# EPass_2026-04-09_20-28-50.net
KiCad netlist of a schematic drawn in EasyEDA Pro
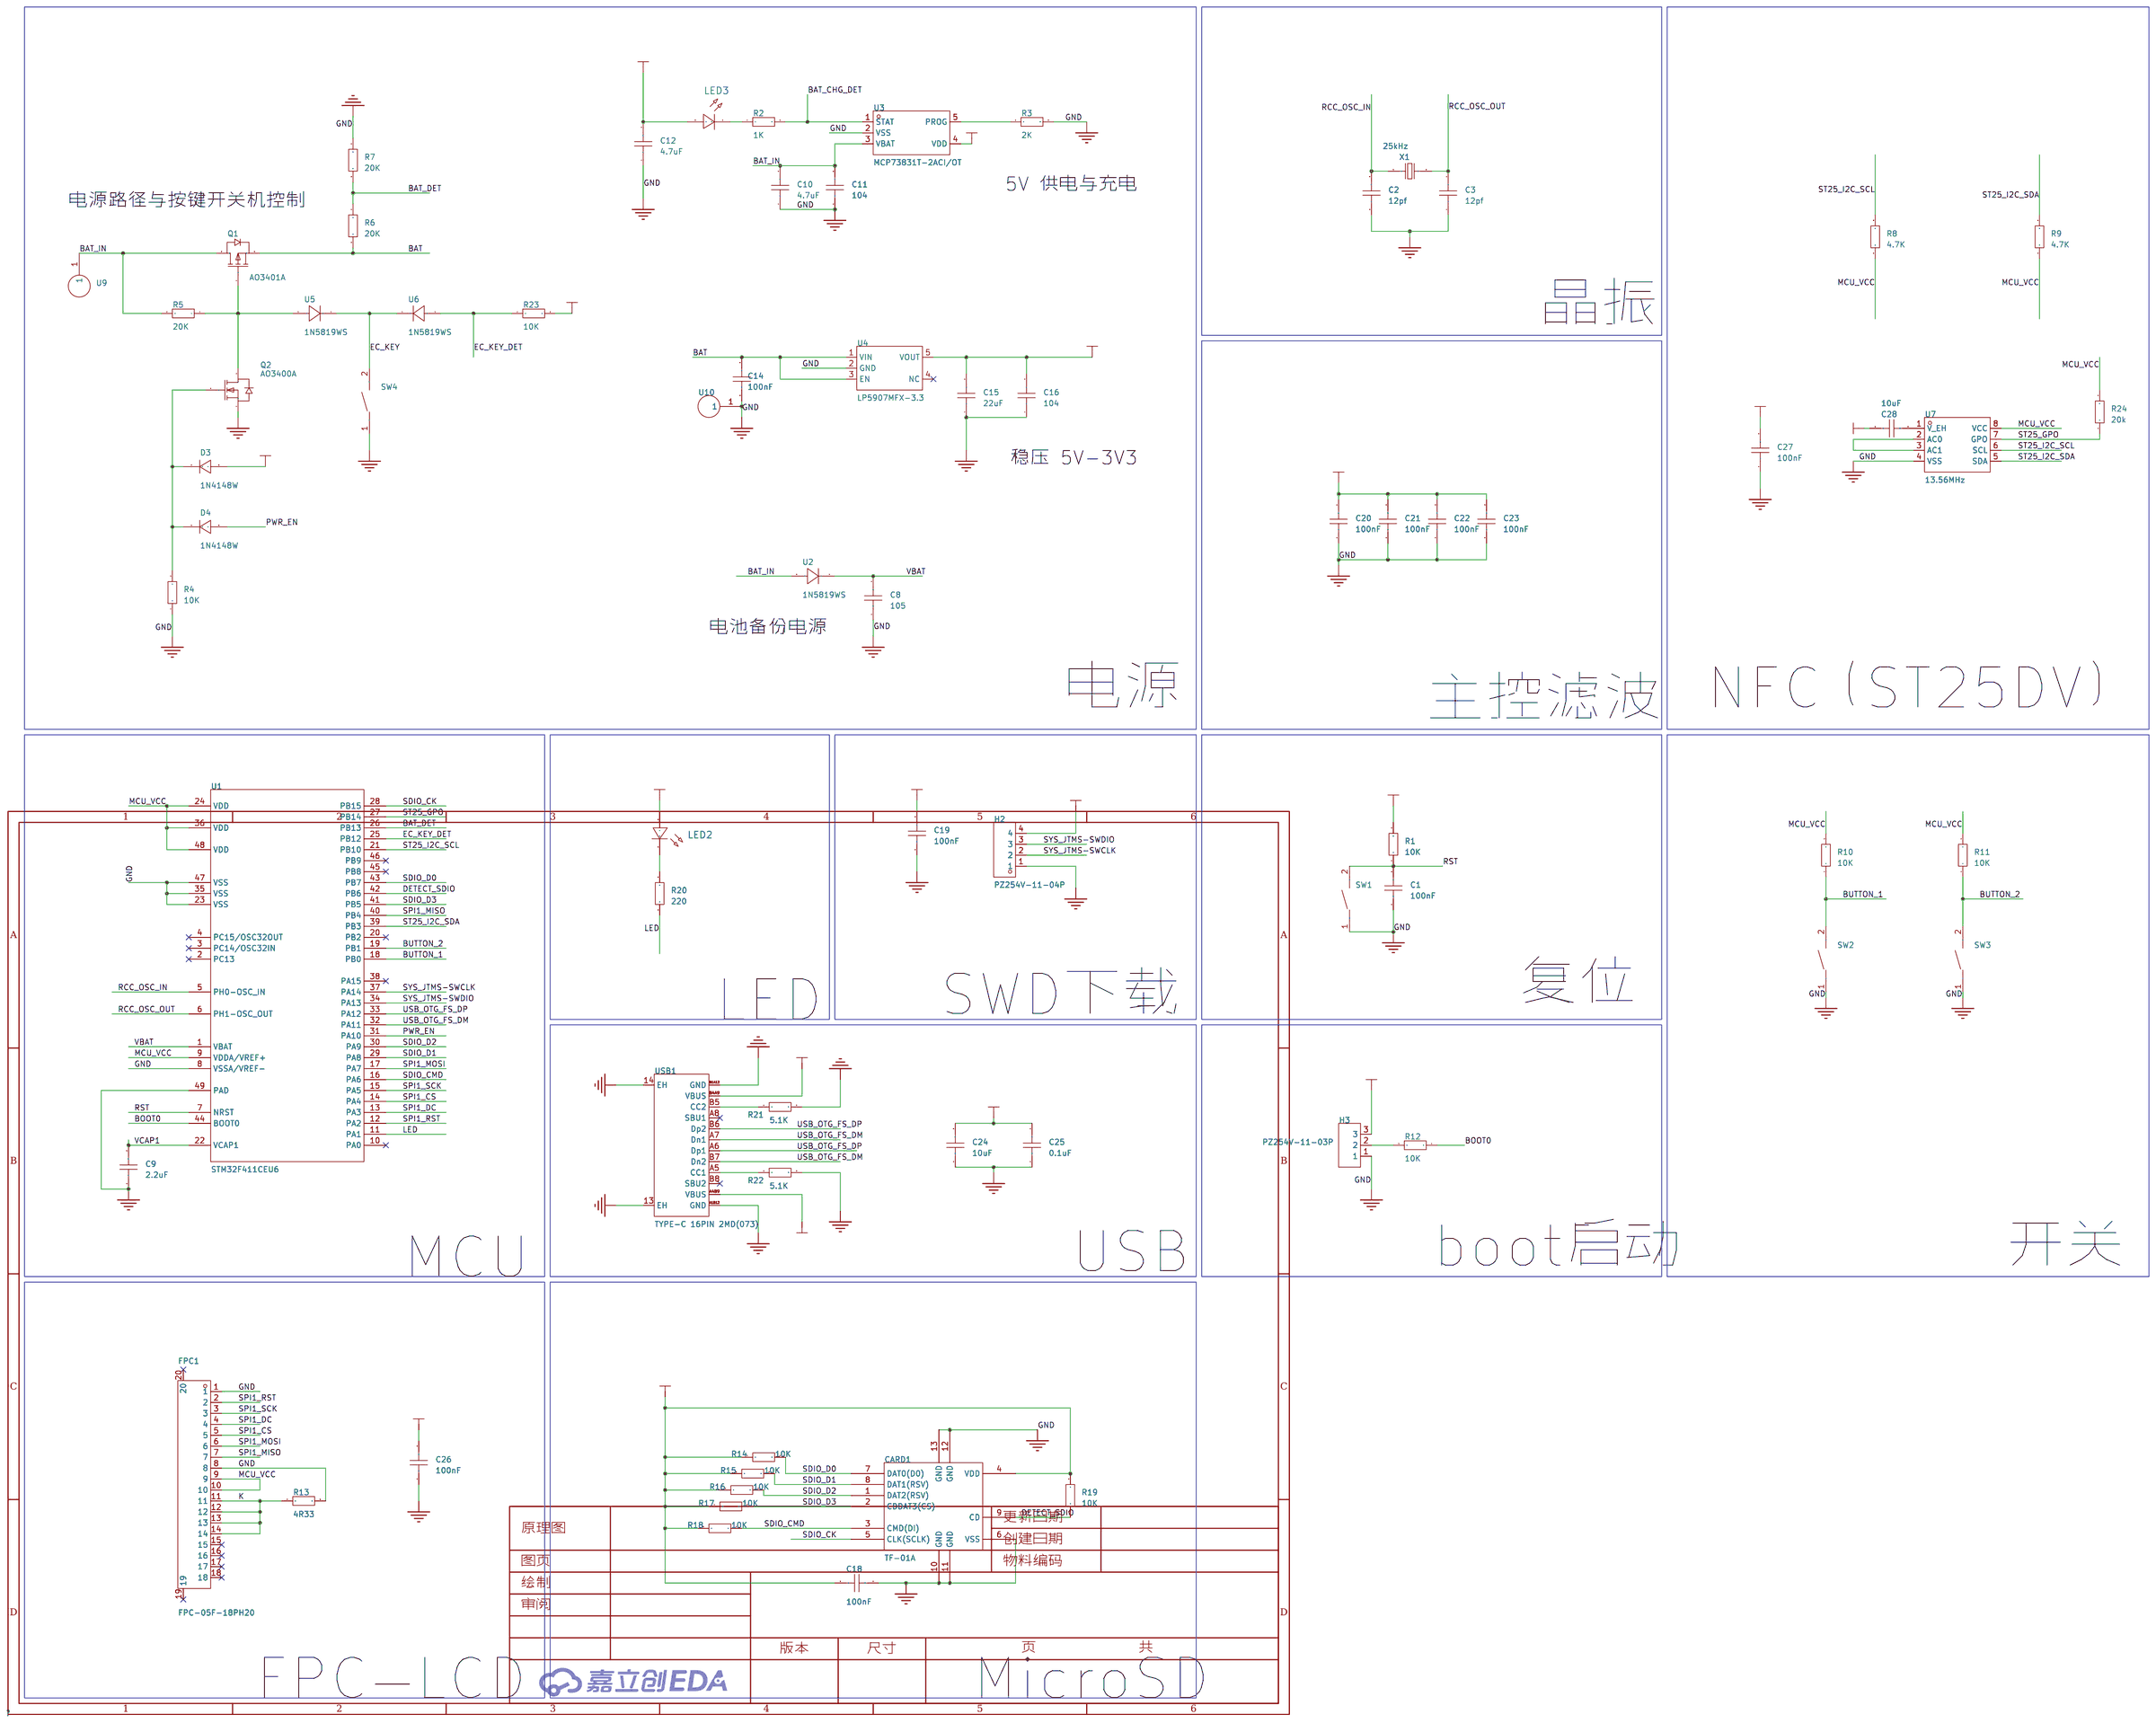
[diagram p0: schematic sheet]

(export (version "E")
  (design (tool "Eeschema 10.0.6"))
  (components
    (comp (ref "C1")
      (value "100nF")
      (footprint "easyedapro:C0603")
      (libsource (lib "easyedapro") (part "Capacitance"))
    )
    (comp (ref "C2")
      (value "12pf")
      (footprint "easyedapro:C0603")
      (libsource (lib "easyedapro") (part "Capacitance"))
    )
    (comp (ref "C3")
      (value "12pf")
      (footprint "easyedapro:C0603")
      (libsource (lib "easyedapro") (part "Capacitance"))
    )
    (comp (ref "C8")
      (value "105")
      (footprint "easyedapro:C0603")
      (libsource (lib "easyedapro") (part "Capacitance"))
    )
    (comp (ref "C9")
      (value "2.2uF")
      (footprint "easyedapro:C0603")
      (libsource (lib "easyedapro") (part "Capacitance"))
    )
    (comp (ref "C10")
      (value "4.7uF")
      (footprint "easyedapro:C0603")
      (libsource (lib "easyedapro") (part "Capacitance"))
    )
    (comp (ref "C11")
      (value "104")
      (footprint "easyedapro:C0603")
      (libsource (lib "easyedapro") (part "Capacitance"))
    )
    (comp (ref "C12")
      (value "4.7uF")
      (footprint "easyedapro:C0603")
      (libsource (lib "easyedapro") (part "Capacitance"))
    )
    (comp (ref "C14")
      (value "100nF")
      (footprint "easyedapro:C0603")
      (libsource (lib "easyedapro") (part "Capacitance"))
    )
    (comp (ref "C15")
      (value "22uF")
      (footprint "easyedapro:C0603")
      (libsource (lib "easyedapro") (part "Capacitance"))
    )
    (comp (ref "C16")
      (value "104")
      (footprint "easyedapro:C0603")
      (libsource (lib "easyedapro") (part "Capacitance"))
    )
    (comp (ref "C18")
      (value "100nF")
      (footprint "easyedapro:C0603")
      (libsource (lib "easyedapro") (part "Capacitance"))
    )
    (comp (ref "C19")
      (value "100nF")
      (footprint "easyedapro:C0603")
      (libsource (lib "easyedapro") (part "Capacitance"))
    )
    (comp (ref "C20")
      (value "100nF")
      (footprint "easyedapro:C0603")
      (libsource (lib "easyedapro") (part "Capacitance"))
    )
    (comp (ref "C21")
      (value "100nF")
      (footprint "easyedapro:C0603")
      (libsource (lib "easyedapro") (part "Capacitance"))
    )
    (comp (ref "C22")
      (value "100nF")
      (footprint "easyedapro:C0603")
      (libsource (lib "easyedapro") (part "Capacitance"))
    )
    (comp (ref "C23")
      (value "100nF")
      (footprint "easyedapro:C0603")
      (libsource (lib "easyedapro") (part "Capacitance"))
    )
    (comp (ref "C24")
      (value "10uF")
      (footprint "easyedapro:C0603")
      (libsource (lib "easyedapro") (part "Capacitance"))
    )
    (comp (ref "C25")
      (value "0.1uF")
      (footprint "easyedapro:C0603")
      (libsource (lib "easyedapro") (part "Capacitance"))
    )
    (comp (ref "C26")
      (value "100nF")
      (footprint "easyedapro:C0603")
      (libsource (lib "easyedapro") (part "Capacitance"))
    )
    (comp (ref "C27")
      (value "100nF")
      (footprint "easyedapro:C0603")
      (libsource (lib "easyedapro") (part "Capacitance"))
    )
    (comp (ref "C28")
      (value "10uF")
      (footprint "easyedapro:C0603")
      (libsource (lib "easyedapro") (part "Capacitance"))
    )
    (comp (ref "CARD1")
      (value "TF-01A")
      (footprint "easyedapro:TF-SMD_TF-01A")
      (description "卡连接方式:自弹式;卡类型:MicroSD卡(TF卡);连接器类型:卡座;本体最大高度:1.85mm;工作温度:-;")
      (fields (field (name "Manufacturer") "韩国韩荣"))
      (libsource (lib "easyedapro") (part "TF-01A"))
    )
    (comp (ref "D3")
      (value "1N4148W")
      (footprint "easyedapro:DO-35_BD2.0-L4.2-P8.20-D0.5-RD")
      (description "二极管配置:1个独立式;整流电流:200mA;直流反向耐压(Vr):100V;正向压降(Vf):1V@10mA;反向恢复时间(Trr):4ns;")
      (fields (field (name "Manufacturer") "R+O(宏嘉诚)"))
      (libsource (lib "easyedapro") (part "1N4148TR"))
    )
    (comp (ref "D4")
      (value "1N4148W")
      (footprint "easyedapro:DO-35_BD2.0-L4.2-P8.20-D0.5-RD")
      (description "二极管配置:1个独立式;整流电流:200mA;直流反向耐压(Vr):100V;正向压降(Vf):1V@10mA;反向恢复时间(Trr):4ns;")
      (fields (field (name "Manufacturer") "R+O(宏嘉诚)"))
      (libsource (lib "easyedapro") (part "1N4148TR"))
    )
    (comp (ref "FPC1")
      (value "FPC-05F-18PH20")
      (footprint "easyedapro:FPC-SMD_18P-P0.50_FPC-05F-18PH20")
      (description "锁定特性:翻盖式;触点类型:卧贴;触点数量:18P;间距:0.5mm;安装方式:下接;工作温度:-25°C~+85°C;")
      (fields (field (name "Manufacturer") "XUNPU(讯普)"))
      (libsource (lib "easyedapro") (part "FPC-05F-18PH20"))
    )
    (comp (ref "H2")
      (value "PZ254V-11-04P")
      (footprint "easyedapro:HDR-TH_4P-P2.54-V-M")
      (fields (field (name "Manufacturer") "XFCN(兴飞)"))
      (libsource (lib "easyedapro") (part "PZ254V-11-04P_C2691448"))
    )
    (comp (ref "H3")
      (value "PZ254V-11-03P")
      (footprint "easyedapro:HDR-TH_3P-P2.54-V-M_PZ254V-11-03P")
      (fields (field (name "Manufacturer") "XFCN(兴飞)"))
      (libsource (lib "easyedapro") (part "PZ254V-11-03P_C2937625"))
    )
    (comp (ref "LED2")
      (value "~")
      (footprint "easyedapro:LED_0603")
      (libsource (lib "easyedapro") (part "LED_R"))
    )
    (comp (ref "LED3")
      (value "~")
      (footprint "easyedapro:LED_0603")
      (libsource (lib "easyedapro") (part "LED_R"))
    )
    (comp (ref "Q1")
      (value "AO3401A")
      (footprint "easyedapro:SOT-23_L2.9-W1.3-P1.90-LS2.4-BR")
      (fields (field (name "Manufacturer") "AOS"))
      (libsource (lib "easyedapro") (part "AO3401A"))
    )
    (comp (ref "Q2")
      (value "AO3400A")
      (footprint "easyedapro:SOT-23-3_L2.9-W1.3-P1.90-LS2.4-BR")
      (description "数量:-;漏源电压(Vdss):30V;连续漏极电流(Id):-;导通电阻(RDS(on)):48mΩ@2.5V;耗散功率(Pd):-;阈值电压(Vgs(th)):1.45V@250uA;")
      (fields (field (name "Manufacturer") "AOS"))
      (libsource (lib "easyedapro") (part "AO3400A"))
    )
    (comp (ref "R1") (value "10K") (footprint "easyedapro:R0603") (libsource (lib "easyedapro") (part "电阻")))
    (comp (ref "R2") (value "1K") (footprint "easyedapro:R0603") (libsource (lib "easyedapro") (part "电阻")))
    (comp (ref "R3") (value "2K") (footprint "easyedapro:R0603") (libsource (lib "easyedapro") (part "电阻")))
    (comp (ref "R4") (value "10K") (footprint "easyedapro:R0603") (libsource (lib "easyedapro") (part "电阻")))
    (comp (ref "R5") (value "20K") (footprint "easyedapro:R0603") (libsource (lib "easyedapro") (part "电阻")))
    (comp (ref "R6") (value "20K") (footprint "easyedapro:R0603") (libsource (lib "easyedapro") (part "电阻")))
    (comp (ref "R7") (value "20K") (footprint "easyedapro:R0603") (libsource (lib "easyedapro") (part "电阻")))
    (comp (ref "R8") (value "4.7K") (footprint "easyedapro:R0603") (libsource (lib "easyedapro") (part "电阻")))
    (comp (ref "R9") (value "4.7K") (footprint "easyedapro:R0603") (libsource (lib "easyedapro") (part "电阻")))
    (comp (ref "R10") (value "10K") (footprint "easyedapro:R0603") (libsource (lib "easyedapro") (part "电阻")))
    (comp (ref "R11") (value "10K") (footprint "easyedapro:R0603") (libsource (lib "easyedapro") (part "电阻")))
    (comp (ref "R12") (value "10K") (footprint "easyedapro:R0603") (libsource (lib "easyedapro") (part "电阻")))
    (comp (ref "R13")
      (value "4R33")
      (footprint "easyedapro:R0603")
      (libsource (lib "easyedapro") (part "电阻"))
    )
    (comp (ref "R14") (value "10K") (footprint "easyedapro:R0603") (libsource (lib "easyedapro") (part "电阻")))
    (comp (ref "R15") (value "10K") (footprint "easyedapro:R0603") (libsource (lib "easyedapro") (part "电阻")))
    (comp (ref "R16") (value "10K") (footprint "easyedapro:R0603") (libsource (lib "easyedapro") (part "电阻")))
    (comp (ref "R17") (value "10K") (footprint "easyedapro:R0603") (libsource (lib "easyedapro") (part "电阻")))
    (comp (ref "R18") (value "10K") (footprint "easyedapro:R0603") (libsource (lib "easyedapro") (part "电阻")))
    (comp (ref "R19") (value "10K") (footprint "easyedapro:R0603") (libsource (lib "easyedapro") (part "电阻")))
    (comp (ref "R20") (value "220") (footprint "easyedapro:R0603") (libsource (lib "easyedapro") (part "电阻")))
    (comp (ref "R21")
      (value "5.1K")
      (footprint "easyedapro:R0603")
      (libsource (lib "easyedapro") (part "电阻"))
    )
    (comp (ref "R22")
      (value "5.1K")
      (footprint "easyedapro:R0603")
      (libsource (lib "easyedapro") (part "电阻"))
    )
    (comp (ref "R23") (value "10K") (footprint "easyedapro:R0603") (libsource (lib "easyedapro") (part "电阻")))
    (comp (ref "R24") (value "20k") (footprint "easyedapro:R0603") (libsource (lib "easyedapro") (part "电阻")))
    (comp (ref "SW1")
      (value "TS-1088-AR02016")
      (footprint "easyedapro:SW-SMD_L3.9-W3.0-P4.45")
      (fields (field (name "Manufacturer") "XUNPU(讯普)"))
      (libsource (lib "easyedapro") (part "TS-1088-AR02016"))
    )
    (comp (ref "SW2")
      (value "TS-1088-AR02016")
      (footprint "easyedapro:SW-SMD_L3.9-W3.0-P4.45")
      (fields (field (name "Manufacturer") "XUNPU(讯普)"))
      (libsource (lib "easyedapro") (part "TS-1088-AR02016"))
    )
    (comp (ref "SW3")
      (value "TS-1088-AR02016")
      (footprint "easyedapro:SW-SMD_L3.9-W3.0-P4.45")
      (fields (field (name "Manufacturer") "XUNPU(讯普)"))
      (libsource (lib "easyedapro") (part "TS-1088-AR02016"))
    )
    (comp (ref "SW4")
      (value "TS-1088-AR02016")
      (footprint "easyedapro:SW-SMD_L3.9-W3.0-P4.45")
      (fields (field (name "Manufacturer") "XUNPU(讯普)"))
      (libsource (lib "easyedapro") (part "TS-1088-AR02016"))
    )
    (comp (ref "U1")
      (value "STM32F411CEU6")
      (footprint "easyedapro:UFQFPN-48_L7.0-W7.0-P0.50-BL-EP")
      (description "CPU内核:ARM-M4;CPU最大主频:100MHz;应用领域:-;")
      (fields (field (name "Manufacturer") "ST(意法半导体)"))
      (libsource (lib "easyedapro") (part "STM32F411CEU6"))
    )
    (comp (ref "U2")
      (value "1N5819WS")
      (footprint "easyedapro:SMA_L4.3-W2.6-LS5.1-RD")
      (fields (field (name "Manufacturer") "Hottech(合科泰)"))
      (libsource (lib "easyedapro") (part "1N4007_C9900004759"))
    )
    (comp (ref "U3")
      (value "MCP73831T-2ACI/OT")
      (footprint "easyedapro:SOT-23-5_L3.0-W1.7-P0.95-LS2.8-BL")
      (description "工作电压:3.75V~6V;最大充电电流:550mA;电池类型:锂电池;电池节数:1;")
      (fields (field (name "Manufacturer") "MICROCHIP(美国微芯)"))
      (libsource (lib "easyedapro") (part "MCP73831T-2ACI/OT"))
    )
    (comp (ref "U4")
      (value "LP5907MFX-3.3")
      (footprint "easyedapro:SOT-23-5_L3.0-W1.7-P0.95-LS2.8-BR")
      (description "输出类型:固定;工作电压:5.5V;输出电压:3.3V;输出电流:300mA;电源纹波抑制比(PSRR):75dB@(1kHz);输出极性:正极;")
      (fields (field (name "Manufacturer") "TECH PUBLIC(台舟)"))
      (libsource (lib "easyedapro") (part "LP5907MFX-3.3"))
    )
    (comp (ref "U5")
      (value "1N5819WS")
      (footprint "easyedapro:SMA_L4.3-W2.6-LS5.1-RD")
      (fields (field (name "Manufacturer") "Hottech(合科泰)"))
      (libsource (lib "easyedapro") (part "1N4007_C9900004759"))
    )
    (comp (ref "U6")
      (value "1N5819WS")
      (footprint "easyedapro:SMA_L4.3-W2.6-LS5.1-RD")
      (fields (field (name "Manufacturer") "Hottech(合科泰)"))
      (libsource (lib "easyedapro") (part "1N4007_C9900004759"))
    )
    (comp (ref "U7")
      (value "13.56MHz")
      (footprint "easyedapro:SO-8_L4.9-W3.9-P1.27-LS5.9-BL")
      (description "协议:ISO 15693,NFC;接口类型:I2C;传输速率:53Kbit/s;")
      (fields (field (name "Manufacturer Part") "ST25DV04KC-IE6S3") (field (name "Manufacturer") "ST(意法半导体)"))
      (libsource (lib "easyedapro") (part "ST25DV04KC-IE6S3"))
    )
    (comp (ref "U9") (value "~") (footprint "easyedapro:焊盘") (libsource (lib "easyedapro") (part "焊盘")))
    (comp (ref "U10") (value "~") (footprint "easyedapro:焊盘") (libsource (lib "easyedapro") (part "焊盘")))
    (comp (ref "USB1")
      (value "TYPE-C 16PIN 2MD(073)")
      (footprint "easyedapro:USB-C-SMD_TYPE-C-16PIN-2MD-073")
      (description "连接器类型:Type-C;协议标准:-;公母:母;安装方式:卧贴;触点数量:16P;端口数量:1;额定电流 - 电源:3A;工作温度:-25°C~+85°C;")
      (fields (field (name "Manufacturer") "SHOU HAN(首韩)"))
      (libsource (lib "easyedapro") (part "TYPE-C 16PIN 2MD(073)"))
    )
    (comp (ref "X1")
      (value "25kHz")
      (footprint "easyedapro:FC-135R_L3.2-W1.5")
      (description "晶振类型:贴片晶振;频率:32.768kHz;常温频差:±20ppm;负载电容:12.5pF;")
      (fields (field (name "Manufacturer Part") "Q13FC13500004") (field (name "Manufacturer") "EPSON(爱普生)"))
      (libsource (lib "easyedapro") (part "Q13FC1350000400"))
    )
  )
  (nets
    (net (code "1") (name "+5V") (class "Default")
      (node (ref "C12") (pin "2") (pinfunction "2_2") (pintype "input"))
      (node (ref "C24") (pin "2") (pinfunction "2_2") (pintype "input"))
      (node (ref "C25") (pin "2") (pinfunction "2_2") (pintype "input"))
      (node (ref "D3") (pin "2") (pinfunction "A_2") (pintype "unspecified"))
      (node (ref "LED3") (pin "2") (pinfunction "A_2") (pintype "input"))
      (node (ref "U3") (pin "4") (pinfunction "VDD_4") (pintype "unspecified"))
      (node (ref "USB1") (pin "A4B9") (pinfunction "VBUS_A4B9") (pintype "unspecified"))
      (node (ref "USB1") (pin "B4A9") (pinfunction "VBUS_B4A9") (pintype "unspecified"))
    )
    (net (code "2") (name "/BAT") (class "Default")
      (node (ref "C14") (pin "2") (pinfunction "2_2") (pintype "input"))
      (node (ref "Q1") (pin "2") (pinfunction "S_2") (pintype "unspecified"))
      (node (ref "R6") (pin "2") (pinfunction "2_2") (pintype "input"))
      (node (ref "U4") (pin "1") (pinfunction "VIN_1") (pintype "unspecified"))
      (node (ref "U4") (pin "3") (pinfunction "EN_3") (pintype "unspecified"))
    )
    (net (code "3") (name "/BAT_CHG_DET") (class "Default")
      (node (ref "R2") (pin "2") (pinfunction "2_2") (pintype "input"))
      (node (ref "U3") (pin "1") (pinfunction "STAT_1") (pintype "unspecified"))
    )
    (net (code "4") (name "/BAT_DET") (class "Default")
      (node (ref "R6") (pin "1") (pinfunction "1_1") (pintype "input"))
      (node (ref "R7") (pin "2") (pinfunction "2_2") (pintype "input"))
      (node (ref "U1") (pin "26") (pinfunction "PB13_26") (pintype "unspecified"))
    )
    (net (code "5") (name "/BAT_IN") (class "Default")
      (node (ref "C10") (pin "2") (pinfunction "2_2") (pintype "input"))
      (node (ref "C11") (pin "2") (pinfunction "2_2") (pintype "input"))
      (node (ref "Q1") (pin "3") (pinfunction "D_3") (pintype "unspecified"))
      (node (ref "R5") (pin "2") (pinfunction "2_2") (pintype "input"))
      (node (ref "U2") (pin "2") (pinfunction "A_2") (pintype "unspecified"))
      (node (ref "U3") (pin "3") (pinfunction "VBAT_3") (pintype "unspecified"))
      (node (ref "U9") (pin "1") (pinfunction "1_1") (pintype "input"))
    )
    (net (code "6") (name "/BOOT0") (class "Default")
      (node (ref "R12") (pin "1") (pinfunction "1_1") (pintype "input"))
      (node (ref "U1") (pin "44") (pinfunction "BOOT0_44") (pintype "input"))
    )
    (net (code "7") (name "/BUTTON_1") (class "Default")
      (node (ref "R10") (pin "1") (pinfunction "1_1") (pintype "input"))
      (node (ref "SW2") (pin "2") (pinfunction "2_2") (pintype "unspecified"))
      (node (ref "U1") (pin "18") (pinfunction "PB0_18") (pintype "unspecified"))
    )
    (net (code "8") (name "/BUTTON_2") (class "Default")
      (node (ref "R11") (pin "1") (pinfunction "1_1") (pintype "input"))
      (node (ref "SW3") (pin "2") (pinfunction "2_2") (pintype "unspecified"))
      (node (ref "U1") (pin "19") (pinfunction "PB1_19") (pintype "unspecified"))
    )
    (net (code "9") (name "/DETECT_SDIO") (class "Default")
      (node (ref "CARD1") (pin "9") (pinfunction "CD_9") (pintype "input"))
      (node (ref "R19") (pin "1") (pinfunction "1_1") (pintype "input"))
      (node (ref "U1") (pin "42") (pinfunction "PB6_42") (pintype "unspecified"))
    )
    (net (code "10") (name "/EC_KEY") (class "Default")
      (node (ref "SW4") (pin "2") (pinfunction "2_2") (pintype "unspecified"))
      (node (ref "U5") (pin "1") (pinfunction "K_1") (pintype "unspecified"))
      (node (ref "U6") (pin "1") (pinfunction "K_1") (pintype "unspecified"))
    )
    (net (code "11") (name "/EC_KEY_DET") (class "Default")
      (node (ref "R23") (pin "1") (pinfunction "1_1") (pintype "input"))
      (node (ref "U1") (pin "25") (pinfunction "PB12_25") (pintype "unspecified"))
      (node (ref "U6") (pin "2") (pinfunction "A_2") (pintype "unspecified"))
    )
    (net (code "12") (name "/K") (class "Default")
      (node (ref "FPC1") (pin "11") (pinfunction "11_11") (pintype "unspecified"))
      (node (ref "FPC1") (pin "12") (pinfunction "12_12") (pintype "unspecified"))
      (node (ref "FPC1") (pin "13") (pinfunction "13_13") (pintype "unspecified"))
      (node (ref "FPC1") (pin "14") (pinfunction "14_14") (pintype "unspecified"))
      (node (ref "R13") (pin "1") (pinfunction "1_1") (pintype "input"))
    )
    (net (code "13") (name "/LED") (class "Default")
      (node (ref "R20") (pin "1") (pinfunction "1_1") (pintype "input"))
      (node (ref "U1") (pin "11") (pinfunction "PA1_11") (pintype "unspecified"))
    )
    (net (code "14") (name "/PWR_EN") (class "Default")
      (node (ref "D4") (pin "2") (pinfunction "A_2") (pintype "unspecified"))
      (node (ref "U1") (pin "31") (pinfunction "PA10_31") (pintype "unspecified"))
    )
    (net (code "15") (name "/RCC_OSC_IN") (class "Default")
      (node (ref "C2") (pin "2") (pinfunction "2_2") (pintype "input"))
      (node (ref "U1") (pin "5") (pinfunction "PH0-OSC_IN_5") (pintype "unspecified"))
      (node (ref "X1") (pin "1") (pinfunction "1_1") (pintype "unspecified"))
    )
    (net (code "16") (name "/RCC_OSC_OUT") (class "Default")
      (node (ref "C3") (pin "2") (pinfunction "2_2") (pintype "input"))
      (node (ref "U1") (pin "6") (pinfunction "PH1-OSC_OUT_6") (pintype "unspecified"))
      (node (ref "X1") (pin "2") (pinfunction "2_2") (pintype "unspecified"))
    )
    (net (code "17") (name "/RST") (class "Default")
      (node (ref "C1") (pin "2") (pinfunction "2_2") (pintype "input"))
      (node (ref "R1") (pin "1") (pinfunction "1_1") (pintype "input"))
      (node (ref "SW1") (pin "2") (pinfunction "2_2") (pintype "unspecified"))
      (node (ref "U1") (pin "7") (pinfunction "NRST_7") (pintype "unspecified"))
    )
    (net (code "18") (name "/SDIO_CK") (class "Default")
      (node (ref "CARD1") (pin "5") (pinfunction "CLK(SCLK)_5") (pintype "input"))
      (node (ref "U1") (pin "28") (pinfunction "PB15_28") (pintype "unspecified"))
    )
    (net (code "19") (name "/SDIO_CMD") (class "Default")
      (node (ref "CARD1") (pin "3") (pinfunction "CMD(DI)_3") (pintype "input"))
      (node (ref "R18") (pin "2") (pinfunction "2_2") (pintype "input"))
      (node (ref "U1") (pin "16") (pinfunction "PA6_16") (pintype "unspecified"))
    )
    (net (code "20") (name "/SDIO_D0") (class "Default")
      (node (ref "CARD1") (pin "7") (pinfunction "DAT0(D0)_7") (pintype "bidirectional"))
      (node (ref "R14") (pin "2") (pinfunction "2_2") (pintype "input"))
      (node (ref "U1") (pin "43") (pinfunction "PB7_43") (pintype "unspecified"))
    )
    (net (code "21") (name "/SDIO_D1") (class "Default")
      (node (ref "CARD1") (pin "8") (pinfunction "DAT1(RSV)_8") (pintype "bidirectional"))
      (node (ref "R15") (pin "2") (pinfunction "2_2") (pintype "input"))
      (node (ref "U1") (pin "29") (pinfunction "PA8_29") (pintype "unspecified"))
    )
    (net (code "22") (name "/SDIO_D2") (class "Default")
      (node (ref "CARD1") (pin "1") (pinfunction "DAT2(RSV)_1") (pintype "bidirectional"))
      (node (ref "R16") (pin "2") (pinfunction "2_2") (pintype "input"))
      (node (ref "U1") (pin "30") (pinfunction "PA9_30") (pintype "unspecified"))
    )
    (net (code "23") (name "/SDIO_D3") (class "Default")
      (node (ref "CARD1") (pin "2") (pinfunction "CDDAT3(CS)_2") (pintype "bidirectional"))
      (node (ref "R17") (pin "2") (pinfunction "2_2") (pintype "input"))
      (node (ref "U1") (pin "41") (pinfunction "PB5_41") (pintype "unspecified"))
    )
    (net (code "24") (name "/SPI1_CS") (class "Default")
      (node (ref "FPC1") (pin "5") (pinfunction "5_5") (pintype "unspecified"))
      (node (ref "U1") (pin "14") (pinfunction "PA4_14") (pintype "unspecified"))
    )
    (net (code "25") (name "/SPI1_DC") (class "Default")
      (node (ref "FPC1") (pin "4") (pinfunction "4_4") (pintype "unspecified"))
      (node (ref "U1") (pin "13") (pinfunction "PA3_13") (pintype "unspecified"))
    )
    (net (code "26") (name "/SPI1_MISO") (class "Default")
      (node (ref "FPC1") (pin "7") (pinfunction "7_7") (pintype "unspecified"))
      (node (ref "U1") (pin "40") (pinfunction "PB4_40") (pintype "unspecified"))
    )
    (net (code "27") (name "/SPI1_MOSI") (class "Default")
      (node (ref "FPC1") (pin "6") (pinfunction "6_6") (pintype "unspecified"))
      (node (ref "U1") (pin "17") (pinfunction "PA7_17") (pintype "unspecified"))
    )
    (net (code "28") (name "/SPI1_RST") (class "Default")
      (node (ref "FPC1") (pin "2") (pinfunction "2_2") (pintype "unspecified"))
      (node (ref "U1") (pin "12") (pinfunction "PA2_12") (pintype "unspecified"))
    )
    (net (code "29") (name "/SPI1_SCK") (class "Default")
      (node (ref "FPC1") (pin "3") (pinfunction "3_3") (pintype "unspecified"))
      (node (ref "U1") (pin "15") (pinfunction "PA5_15") (pintype "unspecified"))
    )
    (net (code "30") (name "/ST25_GPO") (class "Default")
      (node (ref "R24") (pin "1") (pinfunction "1_1") (pintype "input"))
      (node (ref "U1") (pin "27") (pinfunction "PB14_27") (pintype "unspecified"))
      (node (ref "U7") (pin "7") (pinfunction "GPO_7") (pintype "unspecified"))
    )
    (net (code "31") (name "/ST25_I2C_SCL") (class "Default")
      (node (ref "R8") (pin "2") (pinfunction "2_2") (pintype "input"))
      (node (ref "U1") (pin "21") (pinfunction "PB10_21") (pintype "unspecified"))
      (node (ref "U7") (pin "6") (pinfunction "SCL_6") (pintype "unspecified"))
    )
    (net (code "32") (name "/ST25_I2C_SDA") (class "Default")
      (node (ref "R9") (pin "2") (pinfunction "2_2") (pintype "input"))
      (node (ref "U1") (pin "39") (pinfunction "PB3_39") (pintype "unspecified"))
      (node (ref "U7") (pin "5") (pinfunction "SDA_5") (pintype "unspecified"))
    )
    (net (code "33") (name "/SYS_JTMS-SWCLK") (class "Default")
      (node (ref "H2") (pin "2") (pinfunction "2_2") (pintype "unspecified"))
      (node (ref "U1") (pin "37") (pinfunction "PA14_37") (pintype "unspecified"))
    )
    (net (code "34") (name "/SYS_JTMS-SWDIO") (class "Default")
      (node (ref "H2") (pin "3") (pinfunction "3_3") (pintype "unspecified"))
      (node (ref "U1") (pin "34") (pinfunction "PA13_34") (pintype "unspecified"))
    )
    (net (code "35") (name "/USB_OTG_FS_DM") (class "Default")
      (node (ref "U1") (pin "32") (pinfunction "PA11_32") (pintype "unspecified"))
      (node (ref "USB1") (pin "A7") (pinfunction "Dn1_A7") (pintype "unspecified"))
      (node (ref "USB1") (pin "B7") (pinfunction "Dn2_B7") (pintype "unspecified"))
    )
    (net (code "36") (name "/USB_OTG_FS_DP") (class "Default")
      (node (ref "U1") (pin "33") (pinfunction "PA12_33") (pintype "unspecified"))
      (node (ref "USB1") (pin "A6") (pinfunction "Dp1_A6") (pintype "unspecified"))
      (node (ref "USB1") (pin "B6") (pinfunction "Dp2_B6") (pintype "unspecified"))
    )
    (net (code "37") (name "/VBAT") (class "Default")
      (node (ref "C8") (pin "2") (pinfunction "2_2") (pintype "input"))
      (node (ref "U1") (pin "1") (pinfunction "VBAT_1") (pintype "unspecified"))
      (node (ref "U2") (pin "1") (pinfunction "K_1") (pintype "unspecified"))
    )
    (net (code "38") (name "/VCAP1") (class "Default")
      (node (ref "C9") (pin "2") (pinfunction "2_2") (pintype "input"))
      (node (ref "U1") (pin "22") (pinfunction "VCAP1_22") (pintype "unspecified"))
    )
    (net (code "39") (name "GND") (class "Default")
      (node (ref "C1") (pin "1") (pinfunction "1_1") (pintype "input"))
      (node (ref "C10") (pin "1") (pinfunction "1_1") (pintype "input"))
      (node (ref "C11") (pin "1") (pinfunction "1_1") (pintype "input"))
      (node (ref "C12") (pin "1") (pinfunction "1_1") (pintype "input"))
      (node (ref "C14") (pin "1") (pinfunction "1_1") (pintype "input"))
      (node (ref "C15") (pin "1") (pinfunction "1_1") (pintype "input"))
      (node (ref "C16") (pin "1") (pinfunction "1_1") (pintype "input"))
      (node (ref "C18") (pin "2") (pinfunction "2_2") (pintype "input"))
      (node (ref "C19") (pin "1") (pinfunction "1_1") (pintype "input"))
      (node (ref "C2") (pin "1") (pinfunction "1_1") (pintype "input"))
      (node (ref "C20") (pin "1") (pinfunction "1_1") (pintype "input"))
      (node (ref "C21") (pin "1") (pinfunction "1_1") (pintype "input"))
      (node (ref "C22") (pin "1") (pinfunction "1_1") (pintype "input"))
      (node (ref "C23") (pin "1") (pinfunction "1_1") (pintype "input"))
      (node (ref "C24") (pin "1") (pinfunction "1_1") (pintype "input"))
      (node (ref "C25") (pin "1") (pinfunction "1_1") (pintype "input"))
      (node (ref "C26") (pin "1") (pinfunction "1_1") (pintype "input"))
      (node (ref "C27") (pin "1") (pinfunction "1_1") (pintype "input"))
      (node (ref "C3") (pin "1") (pinfunction "1_1") (pintype "input"))
      (node (ref "C8") (pin "1") (pinfunction "1_1") (pintype "input"))
      (node (ref "C9") (pin "1") (pinfunction "1_1") (pintype "input"))
      (node (ref "CARD1") (pin "10") (pinfunction "GND_10") (pintype "input"))
      (node (ref "CARD1") (pin "11") (pinfunction "GND_11") (pintype "input"))
      (node (ref "CARD1") (pin "12") (pinfunction "GND_12") (pintype "input"))
      (node (ref "CARD1") (pin "13") (pinfunction "GND_13") (pintype "input"))
      (node (ref "CARD1") (pin "6") (pinfunction "VSS_6") (pintype "input"))
      (node (ref "FPC1") (pin "1") (pinfunction "1_1") (pintype "unspecified"))
      (node (ref "FPC1") (pin "8") (pinfunction "8_8") (pintype "unspecified"))
      (node (ref "H2") (pin "1") (pinfunction "1_1") (pintype "unspecified"))
      (node (ref "H3") (pin "1") (pinfunction "1_1") (pintype "unspecified"))
      (node (ref "Q2") (pin "2") (pinfunction "S_2") (pintype "unspecified"))
      (node (ref "R13") (pin "2") (pinfunction "2_2") (pintype "input"))
      (node (ref "R21") (pin "2") (pinfunction "2_2") (pintype "input"))
      (node (ref "R22") (pin "2") (pinfunction "2_2") (pintype "input"))
      (node (ref "R3") (pin "2") (pinfunction "2_2") (pintype "input"))
      (node (ref "R4") (pin "1") (pinfunction "1_1") (pintype "input"))
      (node (ref "R7") (pin "1") (pinfunction "1_1") (pintype "input"))
      (node (ref "SW1") (pin "1") (pinfunction "1_1") (pintype "unspecified"))
      (node (ref "SW2") (pin "1") (pinfunction "1_1") (pintype "unspecified"))
      (node (ref "SW3") (pin "1") (pinfunction "1_1") (pintype "unspecified"))
      (node (ref "SW4") (pin "1") (pinfunction "1_1") (pintype "unspecified"))
      (node (ref "U1") (pin "23") (pinfunction "VSS_23") (pintype "unspecified"))
      (node (ref "U1") (pin "35") (pinfunction "VSS_35") (pintype "unspecified"))
      (node (ref "U1") (pin "47") (pinfunction "VSS_47") (pintype "unspecified"))
      (node (ref "U1") (pin "49") (pinfunction "PAD_49") (pintype "unspecified"))
      (node (ref "U1") (pin "8") (pinfunction "VSSA/VREF-_8") (pintype "unspecified"))
      (node (ref "U10") (pin "1") (pinfunction "1_1") (pintype "input"))
      (node (ref "U3") (pin "2") (pinfunction "VSS_2") (pintype "unspecified"))
      (node (ref "U4") (pin "2") (pinfunction "GND_2") (pintype "unspecified"))
      (node (ref "U7") (pin "4") (pinfunction "VSS_4") (pintype "unspecified"))
      (node (ref "USB1") (pin "13") (pinfunction "EH_13") (pintype "unspecified"))
      (node (ref "USB1") (pin "14") (pinfunction "EH_14") (pintype "unspecified"))
      (node (ref "USB1") (pin "A1B12") (pinfunction "GND_A1B12") (pintype "unspecified"))
      (node (ref "USB1") (pin "B1A12") (pinfunction "GND_B1A12") (pintype "unspecified"))
    )
    (net (code "40") (name "MCU_VCC") (class "Default")
      (node (ref "C15") (pin "2") (pinfunction "2_2") (pintype "input"))
      (node (ref "C16") (pin "2") (pinfunction "2_2") (pintype "input"))
      (node (ref "C18") (pin "1") (pinfunction "1_1") (pintype "input"))
      (node (ref "C19") (pin "2") (pinfunction "2_2") (pintype "input"))
      (node (ref "C20") (pin "2") (pinfunction "2_2") (pintype "input"))
      (node (ref "C21") (pin "2") (pinfunction "2_2") (pintype "input"))
      (node (ref "C22") (pin "2") (pinfunction "2_2") (pintype "input"))
      (node (ref "C23") (pin "2") (pinfunction "2_2") (pintype "input"))
      (node (ref "C26") (pin "2") (pinfunction "2_2") (pintype "input"))
      (node (ref "C27") (pin "2") (pinfunction "2_2") (pintype "input"))
      (node (ref "C28") (pin "2") (pinfunction "2_2") (pintype "input"))
      (node (ref "CARD1") (pin "4") (pinfunction "VDD_4") (pintype "input"))
      (node (ref "FPC1") (pin "10") (pinfunction "10_10") (pintype "unspecified"))
      (node (ref "FPC1") (pin "9") (pinfunction "9_9") (pintype "unspecified"))
      (node (ref "H2") (pin "4") (pinfunction "4_4") (pintype "unspecified"))
      (node (ref "H3") (pin "3") (pinfunction "3_3") (pintype "unspecified"))
      (node (ref "LED2") (pin "2") (pinfunction "A_2") (pintype "input"))
      (node (ref "R1") (pin "2") (pinfunction "2_2") (pintype "input"))
      (node (ref "R10") (pin "2") (pinfunction "2_2") (pintype "input"))
      (node (ref "R11") (pin "2") (pinfunction "2_2") (pintype "input"))
      (node (ref "R14") (pin "1") (pinfunction "1_1") (pintype "input"))
      (node (ref "R15") (pin "1") (pinfunction "1_1") (pintype "input"))
      (node (ref "R16") (pin "1") (pinfunction "1_1") (pintype "input"))
      (node (ref "R17") (pin "1") (pinfunction "1_1") (pintype "input"))
      (node (ref "R18") (pin "1") (pinfunction "1_1") (pintype "input"))
      (node (ref "R19") (pin "2") (pinfunction "2_2") (pintype "input"))
      (node (ref "R23") (pin "2") (pinfunction "2_2") (pintype "input"))
      (node (ref "R24") (pin "2") (pinfunction "2_2") (pintype "input"))
      (node (ref "R8") (pin "1") (pinfunction "1_1") (pintype "input"))
      (node (ref "R9") (pin "1") (pinfunction "1_1") (pintype "input"))
      (node (ref "U1") (pin "24") (pinfunction "VDD_24") (pintype "unspecified"))
      (node (ref "U1") (pin "36") (pinfunction "VDD_36") (pintype "unspecified"))
      (node (ref "U1") (pin "48") (pinfunction "VDD_48") (pintype "unspecified"))
      (node (ref "U1") (pin "9") (pinfunction "VDDA/VREF+_9") (pintype "unspecified"))
      (node (ref "U4") (pin "5") (pinfunction "VOUT_5") (pintype "unspecified"))
      (node (ref "U7") (pin "8") (pinfunction "VCC_8") (pintype "unspecified"))
    )
    (net (code "41") (name "Net-(D3-C)") (class "Default")
      (node (ref "D3") (pin "1") (pinfunction "C_1") (pintype "unspecified"))
      (node (ref "D4") (pin "1") (pinfunction "C_1") (pintype "unspecified"))
      (node (ref "Q2") (pin "1") (pinfunction "G_1") (pintype "unspecified"))
      (node (ref "R4") (pin "2") (pinfunction "2_2") (pintype "input"))
    )
    (net (code "42") (name "Net-(H3-Pad2)") (class "Default")
      (node (ref "H3") (pin "2") (pinfunction "2_2") (pintype "unspecified"))
      (node (ref "R12") (pin "2") (pinfunction "2_2") (pintype "input"))
    )
    (net (code "43") (name "Net-(LED2-C)") (class "Default")
      (node (ref "LED2") (pin "1") (pinfunction "C_1") (pintype "input"))
      (node (ref "R20") (pin "2") (pinfunction "2_2") (pintype "input"))
    )
    (net (code "44") (name "Net-(LED3-C)") (class "Default")
      (node (ref "LED3") (pin "1") (pinfunction "C_1") (pintype "input"))
      (node (ref "R2") (pin "1") (pinfunction "1_1") (pintype "input"))
    )
    (net (code "45") (name "Net-(Q1-G)") (class "Default")
      (node (ref "Q1") (pin "1") (pinfunction "G_1") (pintype "unspecified"))
      (node (ref "Q2") (pin "3") (pinfunction "D_3") (pintype "unspecified"))
      (node (ref "R5") (pin "1") (pinfunction "1_1") (pintype "input"))
      (node (ref "U5") (pin "2") (pinfunction "A_2") (pintype "unspecified"))
    )
    (net (code "46") (name "Net-(U3-PROG)") (class "Default")
      (node (ref "R3") (pin "1") (pinfunction "1_1") (pintype "input"))
      (node (ref "U3") (pin "5") (pinfunction "PROG_5") (pintype "unspecified"))
    )
    (net (code "47") (name "Net-(U7-AC0)") (class "Default")
      (node (ref "U7") (pin "2") (pinfunction "AC0_2") (pintype "unspecified"))
      (node (ref "U7") (pin "3") (pinfunction "AC1_3") (pintype "unspecified"))
    )
    (net (code "48") (name "Net-(U7-V_EH)") (class "Default")
      (node (ref "C28") (pin "1") (pinfunction "1_1") (pintype "input"))
      (node (ref "U7") (pin "1") (pinfunction "V_EH_1") (pintype "unspecified"))
    )
    (net (code "49") (name "Net-(USB1-CC1)") (class "Default")
      (node (ref "R22") (pin "1") (pinfunction "1_1") (pintype "input"))
      (node (ref "USB1") (pin "A5") (pinfunction "CC1_A5") (pintype "unspecified"))
    )
    (net (code "50") (name "Net-(USB1-CC2)") (class "Default")
      (node (ref "R21") (pin "1") (pinfunction "1_1") (pintype "input"))
      (node (ref "USB1") (pin "B5") (pinfunction "CC2_B5") (pintype "unspecified"))
    )
    (net (code "51") (name "unconnected-(FPC1-Pad15)") (class "Default")
      (node (ref "FPC1") (pin "15") (pinfunction "15_15") (pintype "unspecified+no_connect"))
    )
    (net (code "52") (name "unconnected-(FPC1-Pad16)") (class "Default")
      (node (ref "FPC1") (pin "16") (pinfunction "16_16") (pintype "unspecified+no_connect"))
    )
    (net (code "53") (name "unconnected-(FPC1-Pad17)") (class "Default")
      (node (ref "FPC1") (pin "17") (pinfunction "17_17") (pintype "unspecified+no_connect"))
    )
    (net (code "54") (name "unconnected-(FPC1-Pad18)") (class "Default")
      (node (ref "FPC1") (pin "18") (pinfunction "18_18") (pintype "unspecified+no_connect"))
    )
    (net (code "55") (name "unconnected-(FPC1-Pad19)") (class "Default")
      (node (ref "FPC1") (pin "19") (pinfunction "19_19") (pintype "unspecified+no_connect"))
    )
    (net (code "56") (name "unconnected-(FPC1-Pad20)") (class "Default")
      (node (ref "FPC1") (pin "20") (pinfunction "20_20") (pintype "unspecified+no_connect"))
    )
    (net (code "57") (name "unconnected-(U1-PA0-Pad10)") (class "Default")
      (node (ref "U1") (pin "10") (pinfunction "PA0_10") (pintype "unspecified+no_connect"))
    )
    (net (code "58") (name "unconnected-(U1-PA15-Pad38)") (class "Default")
      (node (ref "U1") (pin "38") (pinfunction "PA15_38") (pintype "unspecified+no_connect"))
    )
    (net (code "59") (name "unconnected-(U1-PB2-Pad20)") (class "Default")
      (node (ref "U1") (pin "20") (pinfunction "PB2_20") (pintype "unspecified+no_connect"))
    )
    (net (code "60") (name "unconnected-(U1-PB8-Pad45)") (class "Default")
      (node (ref "U1") (pin "45") (pinfunction "PB8_45") (pintype "unspecified+no_connect"))
    )
    (net (code "61") (name "unconnected-(U1-PB9-Pad46)") (class "Default")
      (node (ref "U1") (pin "46") (pinfunction "PB9_46") (pintype "unspecified+no_connect"))
    )
    (net (code "62") (name "unconnected-(U1-PC13-Pad2)") (class "Default")
      (node (ref "U1") (pin "2") (pinfunction "PC13_2") (pintype "unspecified+no_connect"))
    )
    (net (code "63") (name "unconnected-(U1-PC14{slash}OSC32IN-Pad3)") (class "Default")
      (node (ref "U1") (pin "3") (pinfunction "PC14/OSC32IN_3") (pintype "unspecified+no_connect"))
    )
    (net (code "64") (name "unconnected-(U1-PC15{slash}OSC32OUT-Pad4)") (class "Default")
      (node (ref "U1") (pin "4") (pinfunction "PC15/OSC32OUT_4") (pintype "unspecified+no_connect"))
    )
    (net (code "65") (name "unconnected-(U4-NC-Pad4)") (class "Default")
      (node (ref "U4") (pin "4") (pinfunction "NC_4") (pintype "unspecified+no_connect"))
    )
    (net (code "66") (name "unconnected-(USB1-SBU1-PadA8)") (class "Default")
      (node (ref "USB1") (pin "A8") (pinfunction "SBU1_A8") (pintype "unspecified+no_connect"))
    )
    (net (code "67") (name "unconnected-(USB1-SBU2-PadB8)") (class "Default")
      (node (ref "USB1") (pin "B8") (pinfunction "SBU2_B8") (pintype "unspecified+no_connect"))
    )
  )
)
